# IRDetector.net
KiCad netlist of a schematic drawn in EAGLE
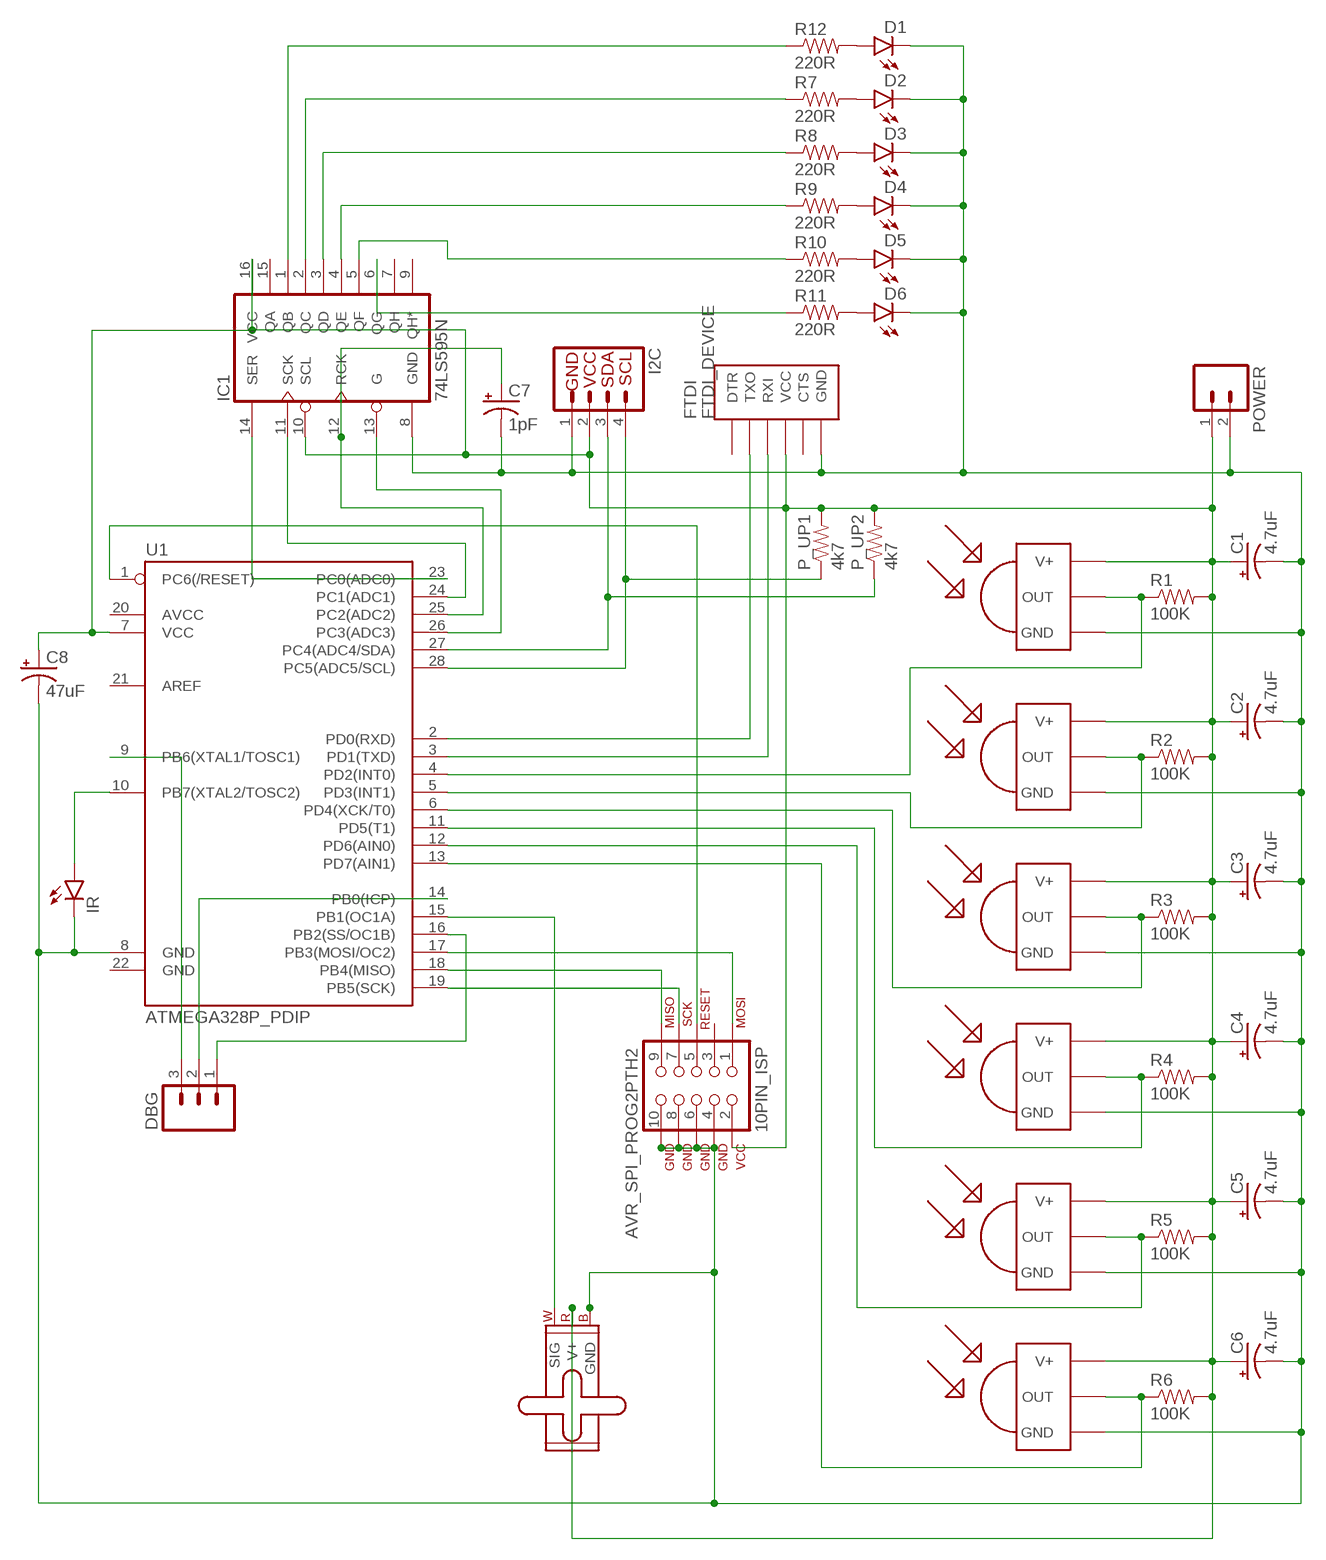
[diagram p0: schematic, sheet 1]

(export (version "E")
  (design (tool "Eeschema 10.0.6"))
  (components
    (comp (ref "10PIN_ISP")
      (value "AVR_SPI_PROG2PTH2")
      (footprint "eagle-import:2X5-SHROUDED")
      (libsource (lib "eagle-import") (part "AVR_SPI_PROG2PTH2"))
    )
    (comp (ref "C1")
      (value "4.7uF")
      (footprint "eagle-import:CPOL-RADIAL-10UF-25V")
      (libsource (lib "eagle-import") (part "CAP_POLPTH2"))
    )
    (comp (ref "C2")
      (value "4.7uF")
      (footprint "eagle-import:CPOL-RADIAL-10UF-25V")
      (libsource (lib "eagle-import") (part "CAP_POLPTH2"))
    )
    (comp (ref "C3")
      (value "4.7uF")
      (footprint "eagle-import:CPOL-RADIAL-10UF-25V")
      (libsource (lib "eagle-import") (part "CAP_POLPTH2"))
    )
    (comp (ref "C4")
      (value "4.7uF")
      (footprint "eagle-import:CPOL-RADIAL-10UF-25V")
      (libsource (lib "eagle-import") (part "CAP_POLPTH2"))
    )
    (comp (ref "C5")
      (value "4.7uF")
      (footprint "eagle-import:CPOL-RADIAL-10UF-25V")
      (libsource (lib "eagle-import") (part "CAP_POLPTH2"))
    )
    (comp (ref "C6")
      (value "4.7uF")
      (footprint "eagle-import:CPOL-RADIAL-10UF-25V")
      (libsource (lib "eagle-import") (part "CAP_POLPTH2"))
    )
    (comp (ref "C7")
      (value "1pF")
      (footprint "eagle-import:CPOL-RADIAL-10UF-25V")
      (libsource (lib "eagle-import") (part "CAP_POLPTH2"))
    )
    (comp (ref "C8")
      (value "47uF")
      (footprint "eagle-import:CPOL-RADIAL-10UF-25V")
      (libsource (lib "eagle-import") (part "CAP_POLPTH2"))
    )
    (comp (ref "D1")
      (value "LED5MM")
      (footprint "eagle-import:LED5MM")
      (libsource (lib "eagle-import") (part "LED5MM"))
    )
    (comp (ref "D2")
      (value "LED5MM")
      (footprint "eagle-import:LED5MM")
      (libsource (lib "eagle-import") (part "LED5MM"))
    )
    (comp (ref "D3")
      (value "LED5MM")
      (footprint "eagle-import:LED5MM")
      (libsource (lib "eagle-import") (part "LED5MM"))
    )
    (comp (ref "D4")
      (value "LED5MM")
      (footprint "eagle-import:LED5MM")
      (libsource (lib "eagle-import") (part "LED5MM"))
    )
    (comp (ref "D5")
      (value "LED5MM")
      (footprint "eagle-import:LED5MM")
      (libsource (lib "eagle-import") (part "LED5MM"))
    )
    (comp (ref "D6")
      (value "LED5MM")
      (footprint "eagle-import:LED5MM")
      (libsource (lib "eagle-import") (part "LED5MM"))
    )
    (comp (ref "DBG")
      (value "M03PTH")
      (footprint "eagle-import:1X03")
      (libsource (lib "eagle-import") (part "M03PTH"))
    )
    (comp (ref "FTDI")
      (value "FTDI_DEVICE")
      (footprint "eagle-import:FTDI_DEVICE_SIDE")
      (libsource (lib "eagle-import") (part "FTDI_DEVICE"))
    )
    (comp (ref "I2C")
      (value "I2C_STANDARD")
      (footprint "eagle-import:1X04")
      (libsource (lib "eagle-import") (part "I2C_STANDARD"))
    )
    (comp (ref "IC1")
      (value "74LS595N")
      (footprint "eagle-import:DIL16")
      (libsource (lib "eagle-import") (part "74595NLS"))
    )
    (comp (ref "IR")
      (value "LED5MM")
      (footprint "eagle-import:LED5MM")
      (libsource (lib "eagle-import") (part "LED5MM"))
    )
    (comp (ref "IRD1")
      (value "TSOP4838")
      (footprint "eagle-import:TSOP18XX")
      (libsource (lib "eagle-import") (part "TSOP4838"))
    )
    (comp (ref "IRD2")
      (value "TSOP4838")
      (footprint "eagle-import:TSOP18XX")
      (libsource (lib "eagle-import") (part "TSOP4838"))
    )
    (comp (ref "IRD3")
      (value "TSOP4838")
      (footprint "eagle-import:TSOP18XX")
      (libsource (lib "eagle-import") (part "TSOP4838"))
    )
    (comp (ref "IRD4")
      (value "TSOP4838")
      (footprint "eagle-import:TSOP18XX")
      (libsource (lib "eagle-import") (part "TSOP4838"))
    )
    (comp (ref "IRD5")
      (value "TSOP4838")
      (footprint "eagle-import:TSOP18XX")
      (libsource (lib "eagle-import") (part "TSOP4838"))
    )
    (comp (ref "IRD6")
      (value "TSOP4838")
      (footprint "eagle-import:TSOP18XX")
      (libsource (lib "eagle-import") (part "TSOP4838"))
    )
    (comp (ref "M1")
      (value "SMALL_SERVO")
      (footprint "eagle-import:1X03")
      (libsource (lib "eagle-import") (part "SMALL_SERVO"))
    )
    (comp (ref "POWER")
      (value "M02JST-PTH-VERT")
      (footprint "eagle-import:JST-2-PTH-VERT")
      (libsource (lib "eagle-import") (part "M02JST-PTH-VERT"))
    )
    (comp (ref "P_UP1")
      (value "4k7")
      (footprint "eagle-import:1_6W-RES")
      (libsource (lib "eagle-import") (part "RESISTORPTH-1/6W"))
    )
    (comp (ref "P_UP2")
      (value "4k7")
      (footprint "eagle-import:1_6W-RES")
      (libsource (lib "eagle-import") (part "RESISTORPTH-1/6W"))
    )
    (comp (ref "R1")
      (value "100K")
      (footprint "eagle-import:1_6W-RES")
      (libsource (lib "eagle-import") (part "RESISTORPTH-1/6W"))
    )
    (comp (ref "R2")
      (value "100K")
      (footprint "eagle-import:1_6W-RES")
      (libsource (lib "eagle-import") (part "RESISTORPTH-1/6W"))
    )
    (comp (ref "R3")
      (value "100K")
      (footprint "eagle-import:1_6W-RES")
      (libsource (lib "eagle-import") (part "RESISTORPTH-1/6W"))
    )
    (comp (ref "R4")
      (value "100K")
      (footprint "eagle-import:1_6W-RES")
      (libsource (lib "eagle-import") (part "RESISTORPTH-1/6W"))
    )
    (comp (ref "R5")
      (value "100K")
      (footprint "eagle-import:1_6W-RES")
      (libsource (lib "eagle-import") (part "RESISTORPTH-1/6W"))
    )
    (comp (ref "R6")
      (value "100K")
      (footprint "eagle-import:1_6W-RES")
      (libsource (lib "eagle-import") (part "RESISTORPTH-1/6W"))
    )
    (comp (ref "R7")
      (value "220R")
      (footprint "eagle-import:1_6W-RES")
      (libsource (lib "eagle-import") (part "RESISTORPTH-1/6W"))
    )
    (comp (ref "R8")
      (value "220R")
      (footprint "eagle-import:1_6W-RES")
      (libsource (lib "eagle-import") (part "RESISTORPTH-1/6W"))
    )
    (comp (ref "R9")
      (value "220R")
      (footprint "eagle-import:1_6W-RES")
      (libsource (lib "eagle-import") (part "RESISTORPTH-1/6W"))
    )
    (comp (ref "R10")
      (value "220R")
      (footprint "eagle-import:1_6W-RES")
      (libsource (lib "eagle-import") (part "RESISTORPTH-1/6W"))
    )
    (comp (ref "R11")
      (value "220R")
      (footprint "eagle-import:1_6W-RES")
      (libsource (lib "eagle-import") (part "RESISTORPTH-1/6W"))
    )
    (comp (ref "R12")
      (value "220R")
      (footprint "eagle-import:1_6W-RES")
      (libsource (lib "eagle-import") (part "RESISTORPTH-1/6W"))
    )
    (comp (ref "U1")
      (value "ATMEGA328P_PDIP")
      (footprint "eagle-import:DIL28-3")
      (libsource (lib "eagle-import") (part "ATMEGA328P_PDIP"))
    )
  )
  (nets
    (net (code "1") (name "Net-(10PIN_ISP-MISO)") (class "Default")
      (node (ref "10PIN_ISP") (pin "9") (pinfunction "MISO_9") (pintype "passive"))
      (node (ref "U1") (pin "18") (pinfunction "PB4(MISO)_18") (pintype "bidirectional"))
    )
    (net (code "2") (name "Net-(10PIN_ISP-MOSI)") (class "Default")
      (node (ref "10PIN_ISP") (pin "1") (pinfunction "MOSI_1") (pintype "passive"))
      (node (ref "U1") (pin "17") (pinfunction "PB3(MOSI/OC2)_17") (pintype "bidirectional"))
    )
    (net (code "3") (name "Net-(10PIN_ISP-RESET)") (class "Default")
      (node (ref "10PIN_ISP") (pin "5") (pinfunction "RESET_5") (pintype "passive"))
      (node (ref "U1") (pin "1") (pinfunction "PC6(/RESET)_1") (pintype "bidirectional"))
    )
    (net (code "4") (name "Net-(10PIN_ISP-SCK)") (class "Default")
      (node (ref "10PIN_ISP") (pin "7") (pinfunction "SCK_7") (pintype "passive"))
      (node (ref "U1") (pin "19") (pinfunction "PB5(SCK)_19") (pintype "bidirectional"))
    )
    (net (code "5") (name "Net-(10PIN_ISP-VCC)") (class "Default")
      (node (ref "10PIN_ISP") (pin "2") (pinfunction "VCC_2") (pintype "power_in"))
      (node (ref "C1") (pin "1") (pinfunction "+_1") (pintype "passive"))
      (node (ref "C2") (pin "1") (pinfunction "+_1") (pintype "passive"))
      (node (ref "C3") (pin "1") (pinfunction "+_1") (pintype "passive"))
      (node (ref "C4") (pin "1") (pinfunction "+_1") (pintype "passive"))
      (node (ref "C5") (pin "1") (pinfunction "+_1") (pintype "passive"))
      (node (ref "C6") (pin "1") (pinfunction "+_1") (pintype "passive"))
      (node (ref "C8") (pin "1") (pinfunction "+_1") (pintype "passive"))
      (node (ref "FTDI") (pin "P$4") (pinfunction "VCC_P$4") (pintype "bidirectional"))
      (node (ref "I2C") (pin "2") (pinfunction "2_2") (pintype "passive"))
      (node (ref "IC1") (pin "10") (pinfunction "SCL_10") (pintype "input"))
      (node (ref "IC1") (pin "16") (pinfunction "VCC_16") (pintype "power_in"))
      (node (ref "IRD1") (pin "VCC") (pinfunction "V+_VCC") (pintype "bidirectional"))
      (node (ref "IRD2") (pin "VCC") (pinfunction "V+_VCC") (pintype "bidirectional"))
      (node (ref "IRD3") (pin "VCC") (pinfunction "V+_VCC") (pintype "bidirectional"))
      (node (ref "IRD4") (pin "VCC") (pinfunction "V+_VCC") (pintype "bidirectional"))
      (node (ref "IRD5") (pin "VCC") (pinfunction "V+_VCC") (pintype "bidirectional"))
      (node (ref "IRD6") (pin "VCC") (pinfunction "V+_VCC") (pintype "bidirectional"))
      (node (ref "M1") (pin "2") (pinfunction "V+_2") (pintype "bidirectional"))
      (node (ref "POWER") (pin "1") (pinfunction "1_1") (pintype "passive"))
      (node (ref "P_UP1") (pin "2") (pinfunction "2_2") (pintype "passive"))
      (node (ref "P_UP2") (pin "2") (pinfunction "2_2") (pintype "passive"))
      (node (ref "R1") (pin "2") (pinfunction "2_2") (pintype "passive"))
      (node (ref "R2") (pin "2") (pinfunction "2_2") (pintype "passive"))
      (node (ref "R3") (pin "2") (pinfunction "2_2") (pintype "passive"))
      (node (ref "R4") (pin "2") (pinfunction "2_2") (pintype "passive"))
      (node (ref "R5") (pin "2") (pinfunction "2_2") (pintype "passive"))
      (node (ref "R6") (pin "2") (pinfunction "2_2") (pintype "passive"))
      (node (ref "U1") (pin "7") (pinfunction "VCC_7") (pintype "bidirectional"))
    )
    (net (code "6") (name "Net-(C1--)") (class "Default")
      (node (ref "10PIN_ISP") (pin "10") (pinfunction "GND_10") (pintype "power_in"))
      (node (ref "10PIN_ISP") (pin "4") (pinfunction "GND_4") (pintype "power_in"))
      (node (ref "10PIN_ISP") (pin "6") (pinfunction "GND_6") (pintype "power_in"))
      (node (ref "10PIN_ISP") (pin "8") (pinfunction "GND_8") (pintype "power_in"))
      (node (ref "C1") (pin "2") (pinfunction "-_2") (pintype "passive"))
      (node (ref "C2") (pin "2") (pinfunction "-_2") (pintype "passive"))
      (node (ref "C3") (pin "2") (pinfunction "-_2") (pintype "passive"))
      (node (ref "C4") (pin "2") (pinfunction "-_2") (pintype "passive"))
      (node (ref "C5") (pin "2") (pinfunction "-_2") (pintype "passive"))
      (node (ref "C6") (pin "2") (pinfunction "-_2") (pintype "passive"))
      (node (ref "C7") (pin "2") (pinfunction "-_2") (pintype "passive"))
      (node (ref "C8") (pin "2") (pinfunction "-_2") (pintype "passive"))
      (node (ref "D1") (pin "K") (pinfunction "C_K") (pintype "passive"))
      (node (ref "D2") (pin "K") (pinfunction "C_K") (pintype "passive"))
      (node (ref "D3") (pin "K") (pinfunction "C_K") (pintype "passive"))
      (node (ref "D4") (pin "K") (pinfunction "C_K") (pintype "passive"))
      (node (ref "D5") (pin "K") (pinfunction "C_K") (pintype "passive"))
      (node (ref "D6") (pin "K") (pinfunction "C_K") (pintype "passive"))
      (node (ref "FTDI") (pin "P$6") (pinfunction "GND_P$6") (pintype "bidirectional"))
      (node (ref "I2C") (pin "1") (pinfunction "1_1") (pintype "passive"))
      (node (ref "IC1") (pin "8") (pinfunction "GND_8") (pintype "power_in"))
      (node (ref "IR") (pin "K") (pinfunction "C_K") (pintype "passive"))
      (node (ref "IRD1") (pin "GND") (pinfunction "GND_GND") (pintype "bidirectional"))
      (node (ref "IRD2") (pin "GND") (pinfunction "GND_GND") (pintype "bidirectional"))
      (node (ref "IRD3") (pin "GND") (pinfunction "GND_GND") (pintype "bidirectional"))
      (node (ref "IRD4") (pin "GND") (pinfunction "GND_GND") (pintype "bidirectional"))
      (node (ref "IRD5") (pin "GND") (pinfunction "GND_GND") (pintype "bidirectional"))
      (node (ref "IRD6") (pin "GND") (pinfunction "GND_GND") (pintype "bidirectional"))
      (node (ref "M1") (pin "3") (pinfunction "GND_3") (pintype "bidirectional"))
      (node (ref "POWER") (pin "2") (pinfunction "2_2") (pintype "passive"))
      (node (ref "U1") (pin "8") (pinfunction "GND_8") (pintype "bidirectional"))
    )
    (net (code "7") (name "Net-(C7-+)") (class "Default")
      (node (ref "C7") (pin "1") (pinfunction "+_1") (pintype "passive"))
      (node (ref "IC1") (pin "12") (pinfunction "RCK_12") (pintype "input"))
      (node (ref "U1") (pin "25") (pinfunction "PC2(ADC2)_25") (pintype "bidirectional"))
    )
    (net (code "8") (name "Net-(D1-PadA)") (class "Default")
      (node (ref "D1") (pin "A") (pinfunction "A_A") (pintype "passive"))
      (node (ref "R12") (pin "2") (pinfunction "2_2") (pintype "passive"))
    )
    (net (code "9") (name "Net-(D2-PadA)") (class "Default")
      (node (ref "D2") (pin "A") (pinfunction "A_A") (pintype "passive"))
      (node (ref "R7") (pin "2") (pinfunction "2_2") (pintype "passive"))
    )
    (net (code "10") (name "Net-(D3-PadA)") (class "Default")
      (node (ref "D3") (pin "A") (pinfunction "A_A") (pintype "passive"))
      (node (ref "R8") (pin "2") (pinfunction "2_2") (pintype "passive"))
    )
    (net (code "11") (name "Net-(D4-PadA)") (class "Default")
      (node (ref "D4") (pin "A") (pinfunction "A_A") (pintype "passive"))
      (node (ref "R9") (pin "2") (pinfunction "2_2") (pintype "passive"))
    )
    (net (code "12") (name "Net-(D5-PadA)") (class "Default")
      (node (ref "D5") (pin "A") (pinfunction "A_A") (pintype "passive"))
      (node (ref "R10") (pin "2") (pinfunction "2_2") (pintype "passive"))
    )
    (net (code "13") (name "Net-(D6-PadA)") (class "Default")
      (node (ref "D6") (pin "A") (pinfunction "A_A") (pintype "passive"))
      (node (ref "R11") (pin "2") (pinfunction "2_2") (pintype "passive"))
    )
    (net (code "14") (name "Net-(FTDI-RXI)") (class "Default")
      (node (ref "FTDI") (pin "P$3") (pinfunction "RXI_P$3") (pintype "bidirectional"))
      (node (ref "U1") (pin "3") (pinfunction "PD1(TXD)_3") (pintype "bidirectional"))
    )
    (net (code "15") (name "Net-(FTDI-TXO)") (class "Default")
      (node (ref "FTDI") (pin "P$2") (pinfunction "TXO_P$2") (pintype "bidirectional"))
      (node (ref "U1") (pin "2") (pinfunction "PD0(RXD)_2") (pintype "bidirectional"))
    )
    (net (code "16") (name "Net-(IC1-G)") (class "Default")
      (node (ref "IC1") (pin "13") (pinfunction "G_13") (pintype "input"))
      (node (ref "U1") (pin "26") (pinfunction "PC3(ADC3)_26") (pintype "bidirectional"))
    )
    (net (code "17") (name "Net-(IC1-QB)") (class "Default")
      (node (ref "IC1") (pin "1") (pinfunction "QB_1") (pintype "tri_state"))
      (node (ref "R12") (pin "1") (pinfunction "1_1") (pintype "passive"))
    )
    (net (code "18") (name "Net-(IC1-QC)") (class "Default")
      (node (ref "IC1") (pin "2") (pinfunction "QC_2") (pintype "tri_state"))
      (node (ref "R7") (pin "1") (pinfunction "1_1") (pintype "passive"))
    )
    (net (code "19") (name "Net-(IC1-QD)") (class "Default")
      (node (ref "IC1") (pin "3") (pinfunction "QD_3") (pintype "tri_state"))
      (node (ref "R8") (pin "1") (pinfunction "1_1") (pintype "passive"))
    )
    (net (code "20") (name "Net-(IC1-QE)") (class "Default")
      (node (ref "IC1") (pin "4") (pinfunction "QE_4") (pintype "tri_state"))
      (node (ref "R9") (pin "1") (pinfunction "1_1") (pintype "passive"))
    )
    (net (code "21") (name "Net-(IC1-QF)") (class "Default")
      (node (ref "IC1") (pin "5") (pinfunction "QF_5") (pintype "tri_state"))
      (node (ref "R10") (pin "1") (pinfunction "1_1") (pintype "passive"))
    )
    (net (code "22") (name "Net-(IC1-QG)") (class "Default")
      (node (ref "IC1") (pin "6") (pinfunction "QG_6") (pintype "tri_state"))
      (node (ref "R11") (pin "1") (pinfunction "1_1") (pintype "passive"))
    )
    (net (code "23") (name "Net-(IC1-SCK)") (class "Default")
      (node (ref "IC1") (pin "11") (pinfunction "SCK_11") (pintype "input"))
      (node (ref "U1") (pin "24") (pinfunction "PC1(ADC1)_24") (pintype "bidirectional"))
    )
    (net (code "24") (name "Net-(IC1-SER)") (class "Default")
      (node (ref "IC1") (pin "14") (pinfunction "SER_14") (pintype "input"))
      (node (ref "U1") (pin "23") (pinfunction "PC0(ADC0)_23") (pintype "bidirectional"))
    )
    (net (code "25") (name "Net-(M1-SIG)") (class "Default")
      (node (ref "M1") (pin "1") (pinfunction "SIG_1") (pintype "bidirectional"))
      (node (ref "U1") (pin "15") (pinfunction "PB1(OC1A)_15") (pintype "bidirectional"))
    )
    (net (code "26") (name "Net-(U1-PB0(ICP))") (class "Default")
      (node (ref "DBG") (pin "2") (pinfunction "2_2") (pintype "passive"))
      (node (ref "U1") (pin "14") (pinfunction "PB0(ICP)_14") (pintype "bidirectional"))
    )
    (net (code "27") (name "Net-(U1-PB2(SS{slash}OC1B))") (class "Default")
      (node (ref "DBG") (pin "1") (pinfunction "1_1") (pintype "passive"))
      (node (ref "U1") (pin "16") (pinfunction "PB2(SS/OC1B)_16") (pintype "bidirectional"))
    )
    (net (code "28") (name "Net-(U1-PB6(XTAL1{slash}TOSC1))") (class "Default")
      (node (ref "DBG") (pin "3") (pinfunction "3_3") (pintype "passive"))
      (node (ref "U1") (pin "9") (pinfunction "PB6(XTAL1/TOSC1)_9") (pintype "bidirectional"))
    )
    (net (code "29") (name "Net-(U1-PB7(XTAL2{slash}TOSC2))") (class "Default")
      (node (ref "IR") (pin "A") (pinfunction "A_A") (pintype "passive"))
      (node (ref "U1") (pin "10") (pinfunction "PB7(XTAL2/TOSC2)_10") (pintype "bidirectional"))
    )
    (net (code "30") (name "Net-(U1-PC4(ADC4{slash}SDA))") (class "Default")
      (node (ref "I2C") (pin "3") (pinfunction "3_3") (pintype "passive"))
      (node (ref "P_UP2") (pin "1") (pinfunction "1_1") (pintype "passive"))
      (node (ref "U1") (pin "27") (pinfunction "PC4(ADC4/SDA)_27") (pintype "bidirectional"))
    )
    (net (code "31") (name "Net-(U1-PC5(ADC5{slash}SCL))") (class "Default")
      (node (ref "I2C") (pin "4") (pinfunction "4_4") (pintype "passive"))
      (node (ref "P_UP1") (pin "1") (pinfunction "1_1") (pintype "passive"))
      (node (ref "U1") (pin "28") (pinfunction "PC5(ADC5/SCL)_28") (pintype "bidirectional"))
    )
    (net (code "32") (name "Net-(U1-PD2(INT0))") (class "Default")
      (node (ref "IRD1") (pin "OUT") (pinfunction "OUT_OUT") (pintype "bidirectional"))
      (node (ref "R1") (pin "1") (pinfunction "1_1") (pintype "passive"))
      (node (ref "U1") (pin "4") (pinfunction "PD2(INT0)_4") (pintype "bidirectional"))
    )
    (net (code "33") (name "Net-(U1-PD3(INT1))") (class "Default")
      (node (ref "IRD2") (pin "OUT") (pinfunction "OUT_OUT") (pintype "bidirectional"))
      (node (ref "R2") (pin "1") (pinfunction "1_1") (pintype "passive"))
      (node (ref "U1") (pin "5") (pinfunction "PD3(INT1)_5") (pintype "bidirectional"))
    )
    (net (code "34") (name "Net-(U1-PD4(XCK{slash}T0))") (class "Default")
      (node (ref "IRD3") (pin "OUT") (pinfunction "OUT_OUT") (pintype "bidirectional"))
      (node (ref "R3") (pin "1") (pinfunction "1_1") (pintype "passive"))
      (node (ref "U1") (pin "6") (pinfunction "PD4(XCK/T0)_6") (pintype "bidirectional"))
    )
    (net (code "35") (name "Net-(U1-PD5(T1))") (class "Default")
      (node (ref "IRD4") (pin "OUT") (pinfunction "OUT_OUT") (pintype "bidirectional"))
      (node (ref "R4") (pin "1") (pinfunction "1_1") (pintype "passive"))
      (node (ref "U1") (pin "11") (pinfunction "PD5(T1)_11") (pintype "bidirectional"))
    )
    (net (code "36") (name "Net-(U1-PD6(AIN0))") (class "Default")
      (node (ref "IRD5") (pin "OUT") (pinfunction "OUT_OUT") (pintype "bidirectional"))
      (node (ref "R5") (pin "1") (pinfunction "1_1") (pintype "passive"))
      (node (ref "U1") (pin "12") (pinfunction "PD6(AIN0)_12") (pintype "bidirectional"))
    )
    (net (code "37") (name "Net-(U1-PD7(AIN1))") (class "Default")
      (node (ref "IRD6") (pin "OUT") (pinfunction "OUT_OUT") (pintype "bidirectional"))
      (node (ref "R6") (pin "1") (pinfunction "1_1") (pintype "passive"))
      (node (ref "U1") (pin "13") (pinfunction "PD7(AIN1)_13") (pintype "bidirectional"))
    )
    (net (code "38") (name "unconnected-(10PIN_ISP-NC-Pad3)") (class "Default")
      (node (ref "10PIN_ISP") (pin "3") (pinfunction "NC_3") (pintype "no_connect"))
    )
    (net (code "39") (name "unconnected-(FTDI-CTS-PadP$5)") (class "Default")
      (node (ref "FTDI") (pin "P$5") (pinfunction "CTS_P$5") (pintype "bidirectional"))
    )
    (net (code "40") (name "unconnected-(FTDI-DTR-PadP$1)") (class "Default")
      (node (ref "FTDI") (pin "P$1") (pinfunction "DTR_P$1") (pintype "bidirectional"))
    )
    (net (code "41") (name "unconnected-(IC1-QA-Pad15)") (class "Default")
      (node (ref "IC1") (pin "15") (pinfunction "QA_15") (pintype "tri_state"))
    )
    (net (code "42") (name "unconnected-(IC1-QH*-Pad9)") (class "Default")
      (node (ref "IC1") (pin "9") (pinfunction "QH*_9") (pintype "tri_state"))
    )
    (net (code "43") (name "unconnected-(IC1-QH-Pad7)") (class "Default")
      (node (ref "IC1") (pin "7") (pinfunction "QH_7") (pintype "tri_state"))
    )
    (net (code "44") (name "unconnected-(U1-AREF-Pad21)") (class "Default")
      (node (ref "U1") (pin "21") (pinfunction "AREF_21") (pintype "bidirectional"))
    )
    (net (code "45") (name "unconnected-(U1-AVCC-Pad20)") (class "Default")
      (node (ref "U1") (pin "20") (pinfunction "AVCC_20") (pintype "bidirectional"))
    )
    (net (code "46") (name "unconnected-(U1-GND-Pad22)") (class "Default")
      (node (ref "U1") (pin "22") (pinfunction "GND_22") (pintype "bidirectional"))
    )
  )
)
